# GPRS_GNSS.net
KiCad netlist of a schematic drawn in Altium Designer
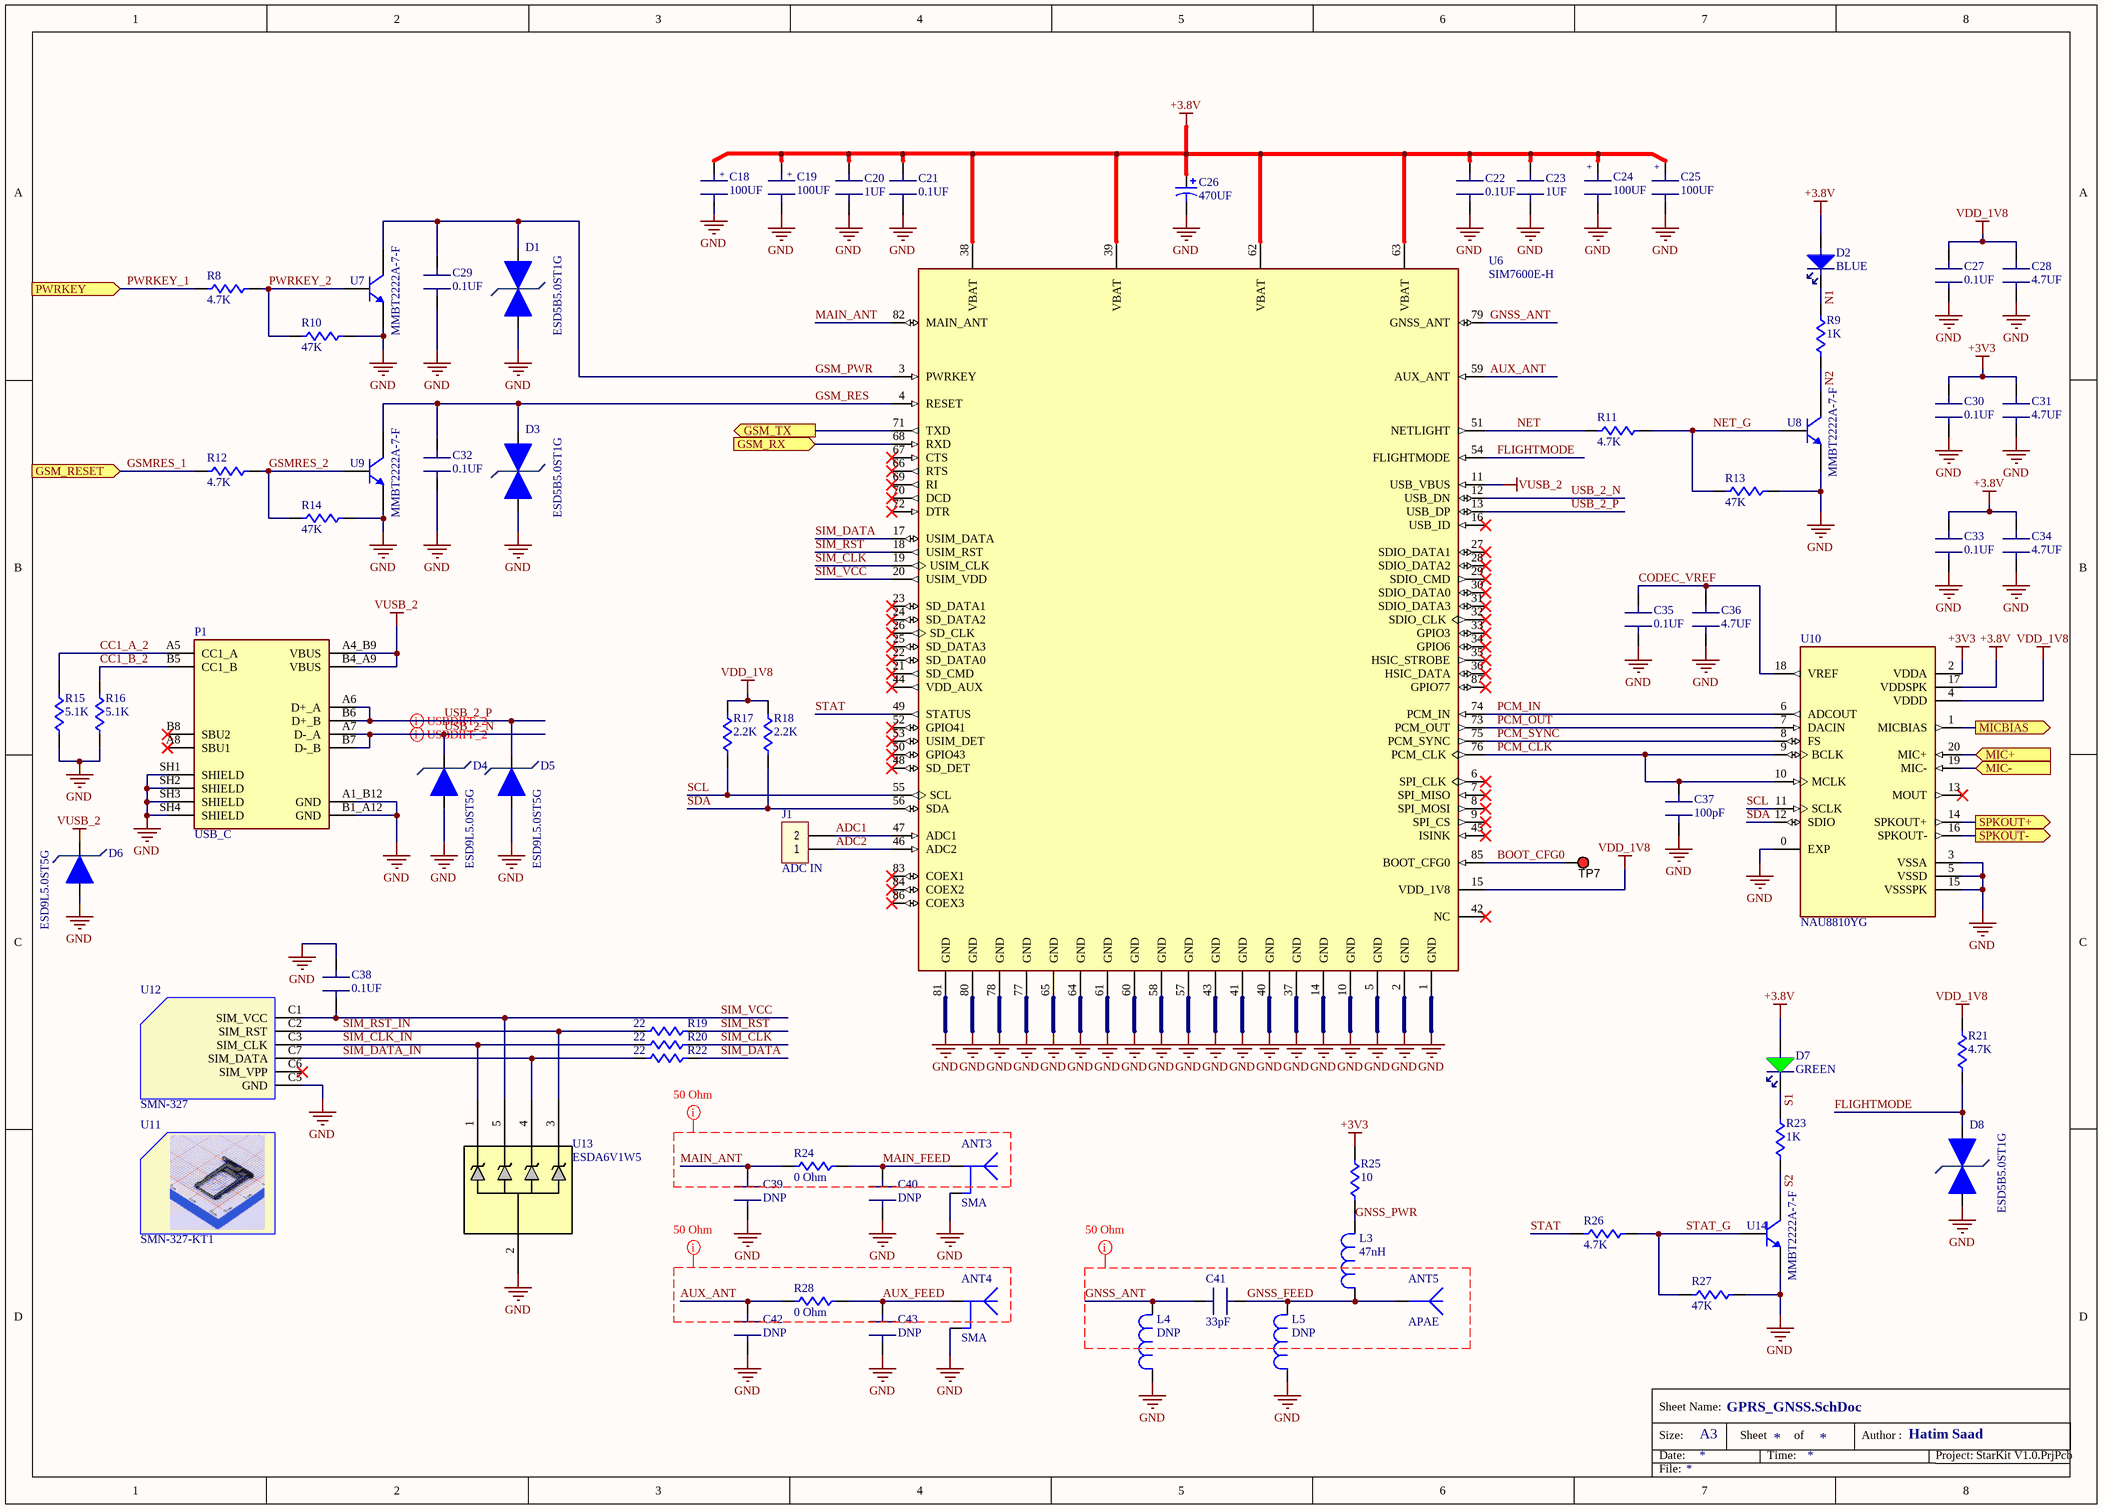
[diagram p0: GPRS_GNSS.SchDoc]

(export (version "E")
  (design (tool "Eeschema 10.0.6"))
  (components
    (comp (ref "ANT3")
      (value "SMA")
      (footprint "SMA RIGHT DIGIKEY")
      (description "Right Angled Female SMA Connector")
      (libsource (lib "HZSchLib") (part "SMA_1"))
    )
    (comp (ref "ANT4")
      (value "SMA")
      (footprint "SMA RIGHT DIGIKEY")
      (description "Right Angled Female SMA Connector")
      (libsource (lib "HZSchLib") (part "SMA_1"))
    )
    (comp (ref "ANT5")
      (value "APAE")
      (footprint "Ceramic Patch Antenna 25x25")
      (description "1575.42MHZ, 25*25*2mm GPS Patch Antenna")
      (fields
        (field (name "MANUFACTURER") "Abracon")
        (field (name "MANUFACTURER PART NUMBER") "APAE1575R2520ABDD7-T")
      )
      (libsource (lib "HZSchLib") (part "APAE1575R2520ABDD7-T"))
    )
    (comp (ref "C18")
      (value "100UF")
      (footprint "CAP: TANTAL-D")
      (description "Tantalum Polymer Capacitor, 100 uF, 16 V, ± 20%, D2, 50 mohm, 2917 [7343-19 Metric]")
      (fields
        (field (name "MANUFACTURER") "Panasonic")
        (field (name "MANUFACTURER PART NUMBER") "16TQC100MYF")
      )
      (libsource (lib "HZSchLib") (part "16TQC100MYF"))
    )
    (comp (ref "C19")
      (value "100UF")
      (footprint "CAP: TANTAL-D")
      (description "Tantalum Polymer Capacitor, 100 uF, 16 V, ± 20%, D2, 50 mohm, 2917 [7343-19 Metric]")
      (fields
        (field (name "MANUFACTURER") "Panasonic")
        (field (name "MANUFACTURER PART NUMBER") "16TQC100MYF")
      )
      (libsource (lib "HZSchLib") (part "16TQC100MYF"))
    )
    (comp (ref "C20")
      (value "1UF")
      (footprint "CAP: 0603")
      (description "CAP SMD 0603")
      (libsource (lib "HZSchLib") (part "CAP 0603"))
    )
    (comp (ref "C21")
      (value "0.1UF")
      (footprint "CAP: 0603")
      (description "CAP SMD 0603")
      (libsource (lib "HZSchLib") (part "CAP 0603"))
    )
    (comp (ref "C22")
      (value "0.1UF")
      (footprint "CAP: 0603")
      (description "CAP SMD 0603")
      (libsource (lib "HZSchLib") (part "CAP 0603"))
    )
    (comp (ref "C23")
      (value "1UF")
      (footprint "CAP: 0603")
      (description "CAP SMD 0603")
      (libsource (lib "HZSchLib") (part "CAP 0603"))
    )
    (comp (ref "C24")
      (value "100UF")
      (footprint "CAP: TANTAL-D")
      (description "Tantalum Polymer Capacitor, 100 uF, 16 V, ± 20%, D2, 50 mohm, 2917 [7343-19 Metric]")
      (fields
        (field (name "MANUFACTURER") "Panasonic")
        (field (name "MANUFACTURER PART NUMBER") "16TQC100MYF")
      )
      (libsource (lib "HZSchLib") (part "16TQC100MYF"))
    )
    (comp (ref "C25")
      (value "100UF")
      (footprint "CAP: TANTAL-D")
      (description "Tantalum Polymer Capacitor, 100 uF, 16 V, ± 20%, D2, 50 mohm, 2917 [7343-19 Metric]")
      (fields
        (field (name "MANUFACTURER") "Panasonic")
        (field (name "MANUFACTURER PART NUMBER") "16TQC100MYF")
      )
      (libsource (lib "HZSchLib") (part "16TQC100MYF"))
    )
    (comp (ref "C26")
      (value "470UF")
      (footprint "CAP POLY: 7.3X4.3X2.8")
      (description "4V 470uF ±20% SMD,4.3x7.3mm Solid Capacitors ROHS")
      (libsource (lib "StarKit V1.0") (part "MPD471M0JD28009R"))
    )
    (comp (ref "C27")
      (value "0.1UF")
      (footprint "CAP: 0603")
      (description "CAP SMD 0603")
      (libsource (lib "HZSchLib") (part "CAP 0603"))
    )
    (comp (ref "C28")
      (value "4.7UF")
      (footprint "CAP: 0805")
      (description "CAP SMD 0805")
      (libsource (lib "HZSchLib") (part "CAP 0805"))
    )
    (comp (ref "C29")
      (value "0.1UF")
      (footprint "CAP: 0603")
      (description "CAP SMD 0603")
      (libsource (lib "HZSchLib") (part "CAP 0603"))
    )
    (comp (ref "C30")
      (value "0.1UF")
      (footprint "CAP: 0603")
      (description "CAP SMD 0603")
      (libsource (lib "HZSchLib") (part "CAP 0603"))
    )
    (comp (ref "C31")
      (value "4.7UF")
      (footprint "CAP: 0805")
      (description "CAP SMD 0805")
      (libsource (lib "HZSchLib") (part "CAP 0805"))
    )
    (comp (ref "C32")
      (value "0.1UF")
      (footprint "CAP: 0603")
      (description "CAP SMD 0603")
      (libsource (lib "HZSchLib") (part "CAP 0603"))
    )
    (comp (ref "C33")
      (value "0.1UF")
      (footprint "CAP: 0603")
      (description "CAP SMD 0603")
      (libsource (lib "HZSchLib") (part "CAP 0603"))
    )
    (comp (ref "C34")
      (value "4.7UF")
      (footprint "CAP: 0805")
      (description "CAP SMD 0805")
      (libsource (lib "HZSchLib") (part "CAP 0805"))
    )
    (comp (ref "C35")
      (value "0.1UF")
      (footprint "CAP: 0603")
      (description "CAP SMD 0603")
      (libsource (lib "HZSchLib") (part "CAP 0603"))
    )
    (comp (ref "C36")
      (value "4.7UF")
      (footprint "CAP: 0805")
      (description "CAP SMD 0805")
      (libsource (lib "HZSchLib") (part "CAP 0805"))
    )
    (comp (ref "C37")
      (value "100pF")
      (footprint "CAP: 0603")
      (description "CAP SMD 0603")
      (libsource (lib "HZSchLib") (part "CAP 0603"))
    )
    (comp (ref "C38")
      (value "0.1UF")
      (footprint "CAP: 0603")
      (description "CAP SMD 0603")
      (libsource (lib "HZSchLib") (part "CAP 0603"))
    )
    (comp (ref "C39")
      (value "DNP")
      (footprint "CAP: 0603")
      (description "CAP SMD 0603")
      (libsource (lib "HZSchLib") (part "CAP 0603"))
    )
    (comp (ref "C40")
      (value "DNP")
      (footprint "CAP: 0603")
      (description "CAP SMD 0603")
      (libsource (lib "HZSchLib") (part "CAP 0603"))
    )
    (comp (ref "C41")
      (value "33pF")
      (footprint "CAP: 0603")
      (description "CAP SMD 0603")
      (libsource (lib "HZSchLib") (part "CAP 0603"))
    )
    (comp (ref "C42")
      (value "DNP")
      (footprint "CAP: 0603")
      (description "CAP SMD 0603")
      (libsource (lib "HZSchLib") (part "CAP 0603"))
    )
    (comp (ref "C43")
      (value "DNP")
      (footprint "CAP: 0603")
      (description "CAP SMD 0603")
      (libsource (lib "HZSchLib") (part "CAP 0603"))
    )
    (comp (ref "D1")
      (value "ESD5B5.0ST1G")
      (footprint "SOD-523-2")
      (description "ESD5B5.0S Series 5.8 V 50 W 32 pF SMT ESD Protection Diode - SOD-523")
      (fields (field (name "MANUFACTURER") "ON Semiconductor"))
      (libsource (lib "HZSchLib") (part "ESD5B5.0ST1G"))
    )
    (comp (ref "D2")
      (value "BLUE")
      (footprint "LED: 0603B")
      (description "LED BLUE CLEAR 0603 SMD")
      (libsource (lib "HZSchLib") (part "LED BLUE 0603"))
    )
    (comp (ref "D3")
      (value "ESD5B5.0ST1G")
      (footprint "SOD-523-2")
      (description "ESD5B5.0S Series 5.8 V 50 W 32 pF SMT ESD Protection Diode - SOD-523")
      (fields (field (name "MANUFACTURER") "ON Semiconductor"))
      (libsource (lib "HZSchLib") (part "ESD5B5.0ST1G"))
    )
    (comp (ref "D4")
      (value "ESD9L5.0ST5G")
      (footprint "SOD-923-2")
      (description "ESD Suppressor Diode TVS Uni-Dir 5V 9.8Vc 2-Pin SOD-923 T/R")
      (fields (field (name "MANUFACTURER") "ON Semiconductor"))
      (libsource (lib "HZSchLib") (part "ESD9L5.0ST5G"))
    )
    (comp (ref "D5")
      (value "ESD9L5.0ST5G")
      (footprint "SOD-923-2")
      (description "ESD Suppressor Diode TVS Uni-Dir 5V 9.8Vc 2-Pin SOD-923 T/R")
      (fields (field (name "MANUFACTURER") "ON Semiconductor"))
      (libsource (lib "HZSchLib") (part "ESD9L5.0ST5G"))
    )
    (comp (ref "D6")
      (value "ESD9L5.0ST5G")
      (footprint "SOD-923-2")
      (description "ESD Suppressor Diode TVS Uni-Dir 5V 9.8Vc 2-Pin SOD-923 T/R")
      (fields (field (name "MANUFACTURER") "ON Semiconductor"))
      (libsource (lib "HZSchLib") (part "ESD9L5.0ST5G"))
    )
    (comp (ref "D7")
      (value "GREEN")
      (footprint "LED: 0603G")
      (description "LED GREEN CLEAR 0603 SMD")
      (libsource (lib "HZSchLib") (part "LED GREEN 0603"))
    )
    (comp (ref "D8")
      (value "ESD5B5.0ST1G")
      (footprint "SOD-523-2")
      (description "ESD5B5.0S Series 5.8 V 50 W 32 pF SMT ESD Protection Diode - SOD-523")
      (fields (field (name "MANUFACTURER") "ON Semiconductor"))
      (libsource (lib "HZSchLib") (part "ESD5B5.0ST1G"))
    )
    (comp (ref "J1")
      (value "ADC IN")
      (footprint "CON: PLS-2")
      (libsource (lib "HZSchLib") (part "CONN 2_HF"))
    )
    (comp (ref "L3")
      (value "47nH")
      (footprint "IND: 0603")
      (description "IND SMD 0603")
      (libsource (lib "HZSchLib") (part "IND 0603"))
    )
    (comp (ref "L4")
      (value "DNP")
      (footprint "IND: 0603")
      (description "IND SMD 0603")
      (libsource (lib "HZSchLib") (part "IND 0603"))
    )
    (comp (ref "L5")
      (value "DNP")
      (footprint "IND: 0603")
      (description "IND SMD 0603")
      (libsource (lib "HZSchLib") (part "IND 0603"))
    )
    (comp (ref "P1")
      (value "USB_C")
      (footprint "AMPHENOL_12402012E212A")
      (description "USB Connectors USB2.0, Type C, Top mount, CH 1.68mm, Dual Row SMT")
      (fields
        (field (name "MANUFACTURER") "Amphenol")
        (field (name "MANUFACTURER PART NUMBER") "12402012E212A")
      )
      (libsource (lib "HZSchLib") (part "12402012E212A"))
    )
    (comp (ref "R8")
      (value "4.7K")
      (footprint "RES: 0603")
      (description "RES SMD 0603")
      (libsource (lib "HZSchLib") (part "RES 0603"))
    )
    (comp (ref "R9")
      (value "1K")
      (footprint "RES: 0603")
      (description "RES SMD 0603")
      (libsource (lib "HZSchLib") (part "RES 0603"))
    )
    (comp (ref "R10")
      (value "47K")
      (footprint "RES: 0603")
      (description "RES SMD 0603")
      (libsource (lib "HZSchLib") (part "RES 0603"))
    )
    (comp (ref "R11")
      (value "4.7K")
      (footprint "RES: 0603")
      (description "RES SMD 0603")
      (libsource (lib "HZSchLib") (part "RES 0603"))
    )
    (comp (ref "R12")
      (value "4.7K")
      (footprint "RES: 0603")
      (description "RES SMD 0603")
      (libsource (lib "HZSchLib") (part "RES 0603"))
    )
    (comp (ref "R13")
      (value "47K")
      (footprint "RES: 0603")
      (description "RES SMD 0603")
      (libsource (lib "HZSchLib") (part "RES 0603"))
    )
    (comp (ref "R14")
      (value "47K")
      (footprint "RES: 0603")
      (description "RES SMD 0603")
      (libsource (lib "HZSchLib") (part "RES 0603"))
    )
    (comp (ref "R15")
      (value "5.1K")
      (footprint "RES: 0603")
      (description "RES SMD 0603")
      (libsource (lib "HZSchLib") (part "RES 0603"))
    )
    (comp (ref "R16")
      (value "5.1K")
      (footprint "RES: 0603")
      (description "RES SMD 0603")
      (libsource (lib "HZSchLib") (part "RES 0603"))
    )
    (comp (ref "R17")
      (value "2.2K")
      (footprint "RES: 0603")
      (description "RES SMD 0603")
      (libsource (lib "HZSchLib") (part "RES 0603"))
    )
    (comp (ref "R18")
      (value "2.2K")
      (footprint "RES: 0603")
      (description "RES SMD 0603")
      (libsource (lib "HZSchLib") (part "RES 0603"))
    )
    (comp (ref "R19")
      (value "22")
      (footprint "RES: 0603")
      (description "RES SMD 0603")
      (libsource (lib "HZSchLib") (part "RES 0603"))
    )
    (comp (ref "R20")
      (value "22")
      (footprint "RES: 0603")
      (description "RES SMD 0603")
      (libsource (lib "HZSchLib") (part "RES 0603"))
    )
    (comp (ref "R21")
      (value "4.7K")
      (footprint "RES: 0603")
      (description "RES SMD 0603")
      (libsource (lib "HZSchLib") (part "RES 0603"))
    )
    (comp (ref "R22")
      (value "22")
      (footprint "RES: 0603")
      (description "RES SMD 0603")
      (libsource (lib "HZSchLib") (part "RES 0603"))
    )
    (comp (ref "R23")
      (value "1K")
      (footprint "RES: 0603")
      (description "RES SMD 0603")
      (libsource (lib "HZSchLib") (part "RES 0603"))
    )
    (comp (ref "R24")
      (value "0 Ohm")
      (footprint "RES: 0603")
      (description "RES SMD 0603")
      (libsource (lib "HZSchLib") (part "RES 0603"))
    )
    (comp (ref "R25")
      (value "10")
      (footprint "RES: 0603")
      (description "RES SMD 0603")
      (libsource (lib "HZSchLib") (part "RES 0603"))
    )
    (comp (ref "R26")
      (value "4.7K")
      (footprint "RES: 0603")
      (description "RES SMD 0603")
      (libsource (lib "HZSchLib") (part "RES 0603"))
    )
    (comp (ref "R27")
      (value "47K")
      (footprint "RES: 0603")
      (description "RES SMD 0603")
      (libsource (lib "HZSchLib") (part "RES 0603"))
    )
    (comp (ref "R28")
      (value "0 Ohm")
      (footprint "RES: 0603")
      (description "RES SMD 0603")
      (libsource (lib "HZSchLib") (part "RES 0603"))
    )
    (comp (ref "TP7")
      (value "5010")
      (footprint "test point")
      (description "Test Point, Multipurpose, Red, TH")
      (fields (field (name "MANUFACTURER") "Keystone") (field (name "PUBLISHER") "Texas Instruments"))
      (libsource (lib "HZSchLib") (part "test point"))
    )
    (comp (ref "U6")
      (value "SIM7600E-H")
      (footprint "SIM7600X")
      (description "RF TXRX MODULE CELLULAR LTE SMD")
      (libsource (lib "HZSchLib") (part "SIM7600E-H"))
    )
    (comp (ref "U7")
      (value "MMBT2222A-7-F")
      (footprint "SOT23_3")
      (description "MMBT2222 Series NPN 350 mW 40 V 600 mA SMT Small Signal Transistor - SOT-23")
      (fields (field (name "MANUFACTURER") "Diodes") (field (name "VOLTAGE") "40V"))
      (libsource (lib "HZSchLib") (part "MMBT2222A-7-F"))
    )
    (comp (ref "U8")
      (value "MMBT2222A-7-F")
      (footprint "SOT23_3")
      (description "MMBT2222 Series NPN 350 mW 40 V 600 mA SMT Small Signal Transistor - SOT-23")
      (fields (field (name "MANUFACTURER") "Diodes") (field (name "VOLTAGE") "40V"))
      (libsource (lib "HZSchLib") (part "MMBT2222A-7-F"))
    )
    (comp (ref "U9")
      (value "MMBT2222A-7-F")
      (footprint "SOT23_3")
      (description "MMBT2222 Series NPN 350 mW 40 V 600 mA SMT Small Signal Transistor - SOT-23")
      (fields (field (name "MANUFACTURER") "Diodes") (field (name "VOLTAGE") "40V"))
      (libsource (lib "HZSchLib") (part "MMBT2222A-7-F"))
    )
    (comp (ref "U10")
      (value "NAU8810YG")
      (footprint "20-QFN (4x4)")
      (description "IC Audio Codec Mono 20QFN")
      (fields (field (name "MANUFACTURER") "Nuvoton"))
      (libsource (lib "HZSchLib") (part "NAU8810YG"))
    )
    (comp (ref "U11")
      (value "SMN-327-KT1")
      (description "NanoSIM tray SIM Card Connectors")
      (fields (field (name "PUBLISHER") "Bastam Beyrami"))
      (libsource (lib "HZSchLib") (part "C390998"))
    )
    (comp (ref "U12")
      (value "SMN-327")
      (footprint "SIM_NANO_SMN-327")
      (description "NanoSIM SMD SIM Card Connectors")
      (fields (field (name "PUBLISHER") "Bastam Beyrami"))
      (libsource (lib "HZSchLib") (part "C390997"))
    )
    (comp (ref "U13")
      (value "ESDA6V1W5")
      (footprint "SOT323-5L")
      (description "ESDA Series 4 Channel 6.1V 90 pF SMT Uni-Directional Transil Array - SOT-323-5L")
      (fields (field (name "MANUFACTURER") "STMicroelectronics"))
      (libsource (lib "HZSchLib") (part "ESDA6V1W5"))
    )
    (comp (ref "U14")
      (value "MMBT2222A-7-F")
      (footprint "SOT23_3")
      (description "MMBT2222 Series NPN 350 mW 40 V 600 mA SMT Small Signal Transistor - SOT-23")
      (fields (field (name "MANUFACTURER") "Diodes") (field (name "VOLTAGE") "40V"))
      (libsource (lib "HZSchLib") (part "MMBT2222A-7-F"))
    )
  )
  (nets
    (net (code "1") (name "+3.8V") (class "Default")
      (node (ref "C18") (pin "1") (pinfunction "+_1") (pintype "passive"))
      (node (ref "C19") (pin "1") (pinfunction "+_1") (pintype "passive"))
      (node (ref "C20") (pin "1") (pinfunction "A_1") (pintype "passive"))
      (node (ref "C21") (pin "1") (pinfunction "A_1") (pintype "passive"))
      (node (ref "C22") (pin "1") (pinfunction "A_1") (pintype "passive"))
      (node (ref "C23") (pin "1") (pinfunction "A_1") (pintype "passive"))
      (node (ref "C24") (pin "1") (pinfunction "+_1") (pintype "passive"))
      (node (ref "C25") (pin "1") (pinfunction "+_1") (pintype "passive"))
      (node (ref "C26") (pin "1") (pinfunction "1_1") (pintype "passive"))
      (node (ref "C33") (pin "1") (pinfunction "A_1") (pintype "passive"))
      (node (ref "C34") (pin "2") (pinfunction "B_2") (pintype "passive"))
      (node (ref "D2") (pin "2") (pinfunction "A_2") (pintype "passive"))
      (node (ref "D7") (pin "2") (pinfunction "A_2") (pintype "passive"))
      (node (ref "U10") (pin "17") (pinfunction "VDDSPK_17") (pintype "power_in"))
      (node (ref "U6") (pin "38") (pinfunction "VBAT_38") (pintype "power_in"))
      (node (ref "U6") (pin "39") (pinfunction "VBAT_39") (pintype "power_in"))
      (node (ref "U6") (pin "62") (pinfunction "VBAT_62") (pintype "power_in"))
      (node (ref "U6") (pin "63") (pinfunction "VBAT_63") (pintype "power_in"))
    )
    (net (code "2") (name "+3V3") (class "Default")
      (node (ref "C30") (pin "1") (pinfunction "A_1") (pintype "passive"))
      (node (ref "C31") (pin "2") (pinfunction "B_2") (pintype "passive"))
      (node (ref "R25") (pin "2") (pinfunction "2_2") (pintype "passive"))
      (node (ref "U10") (pin "2") (pinfunction "VDDA_2") (pintype "power_in"))
    )
    (net (code "3") (name "/ADC1") (class "Default")
      (node (ref "J1") (pin "2") (pinfunction "2_2") (pintype "power_in"))
      (node (ref "U6") (pin "47") (pinfunction "ADC1_47") (pintype "input"))
    )
    (net (code "4") (name "/ADC2") (class "Default")
      (node (ref "J1") (pin "1") (pinfunction "1_1") (pintype "passive"))
      (node (ref "U6") (pin "46") (pinfunction "ADC2_46") (pintype "input"))
    )
    (net (code "5") (name "/AUX_ANT") (class "Default")
      (node (ref "C42") (pin "1") (pinfunction "A_1") (pintype "passive"))
      (node (ref "R28") (pin "1") (pinfunction "1_1") (pintype "passive"))
      (node (ref "U6") (pin "59") (pinfunction "AUX_ANT_59") (pintype "input"))
    )
    (net (code "6") (name "/AUX_FEED") (class "Default")
      (node (ref "ANT4") (pin "1") (pinfunction "1_1") (pintype "passive"))
      (node (ref "C43") (pin "1") (pinfunction "A_1") (pintype "passive"))
      (node (ref "R28") (pin "2") (pinfunction "2_2") (pintype "passive"))
    )
    (net (code "7") (name "/BOOT_CFG0") (class "Default")
      (node (ref "TP7") (pin "1") (pintype "passive"))
      (node (ref "U6") (pin "85") (pinfunction "BOOT_CFG0_85") (pintype "input"))
    )
    (net (code "8") (name "/CC1_A_2") (class "Default")
      (node (ref "P1") (pin "A5") (pinfunction "CC1_A_A5") (pintype "passive"))
      (node (ref "R15") (pin "2") (pinfunction "2_2") (pintype "passive"))
    )
    (net (code "9") (name "/CC1_B_2") (class "Default")
      (node (ref "P1") (pin "B5") (pinfunction "CC1_B_B5") (pintype "passive"))
      (node (ref "R16") (pin "2") (pinfunction "2_2") (pintype "passive"))
    )
    (net (code "10") (name "/CODEC_VREF") (class "Default")
      (node (ref "C35") (pin "1") (pinfunction "A_1") (pintype "passive"))
      (node (ref "C36") (pin "2") (pinfunction "B_2") (pintype "passive"))
      (node (ref "U10") (pin "18") (pinfunction "VREF_18") (pintype "output"))
    )
    (net (code "11") (name "/FLIGHTMODE") (class "Default")
      (node (ref "D8") (pin "1") (pinfunction "1_1") (pintype "passive"))
      (node (ref "R21") (pin "1") (pinfunction "1_1") (pintype "passive"))
      (node (ref "U6") (pin "54") (pinfunction "FLIGHTMODE_54") (pintype "input"))
    )
    (net (code "12") (name "/GNSS_ANT") (class "Default")
      (node (ref "C41") (pin "1") (pinfunction "A_1") (pintype "passive"))
      (node (ref "L4") (pin "2") (pinfunction "2_2") (pintype "passive"))
      (node (ref "U6") (pin "79") (pinfunction "GNSS_ANT_79") (pintype "bidirectional"))
    )
    (net (code "13") (name "/GNSS_FEED") (class "Default")
      (node (ref "ANT5") (pin "1") (pinfunction "1_1") (pintype "passive"))
      (node (ref "C41") (pin "2") (pinfunction "B_2") (pintype "passive"))
      (node (ref "L3") (pin "1") (pinfunction "1_1") (pintype "passive"))
      (node (ref "L5") (pin "2") (pinfunction "2_2") (pintype "passive"))
    )
    (net (code "14") (name "/GNSS_PWR") (class "Default")
      (node (ref "L3") (pin "2") (pinfunction "2_2") (pintype "passive"))
      (node (ref "R25") (pin "1") (pinfunction "1_1") (pintype "passive"))
    )
    (net (code "15") (name "/GSMRES_1") (class "Default")
      (node (ref "R12") (pin "1") (pinfunction "1_1") (pintype "passive"))
    )
    (net (code "16") (name "/GSMRES_2") (class "Default")
      (node (ref "R12") (pin "2") (pinfunction "2_2") (pintype "passive"))
      (node (ref "R14") (pin "1") (pinfunction "1_1") (pintype "passive"))
      (node (ref "U9") (pin "1") (pinfunction "B_1") (pintype "passive"))
    )
    (net (code "17") (name "/GSM_PWR") (class "Default")
      (node (ref "C29") (pin "1") (pinfunction "A_1") (pintype "passive"))
      (node (ref "D1") (pin "1") (pinfunction "1_1") (pintype "passive"))
      (node (ref "U6") (pin "3") (pinfunction "PWRKEY_3") (pintype "input"))
      (node (ref "U7") (pin "3") (pinfunction "C_3") (pintype "passive"))
    )
    (net (code "18") (name "/GSM_RES") (class "Default")
      (node (ref "C32") (pin "1") (pinfunction "A_1") (pintype "passive"))
      (node (ref "D3") (pin "1") (pinfunction "1_1") (pintype "passive"))
      (node (ref "U6") (pin "4") (pinfunction "RESET_4") (pintype "input"))
      (node (ref "U9") (pin "3") (pinfunction "C_3") (pintype "passive"))
    )
    (net (code "19") (name "/GSM_RX") (class "Default")
      (node (ref "U6") (pin "68") (pinfunction "RXD_68") (pintype "input"))
    )
    (net (code "20") (name "/GSM_TX") (class "Default")
      (node (ref "U6") (pin "71") (pinfunction "TXD_71") (pintype "output"))
    )
    (net (code "21") (name "/MAIN_ANT") (class "Default")
      (node (ref "C39") (pin "1") (pinfunction "A_1") (pintype "passive"))
      (node (ref "R24") (pin "1") (pinfunction "1_1") (pintype "passive"))
      (node (ref "U6") (pin "82") (pinfunction "MAIN_ANT_82") (pintype "bidirectional"))
    )
    (net (code "22") (name "/MAIN_FEED") (class "Default")
      (node (ref "ANT3") (pin "1") (pinfunction "1_1") (pintype "passive"))
      (node (ref "C40") (pin "1") (pinfunction "A_1") (pintype "passive"))
      (node (ref "R24") (pin "2") (pinfunction "2_2") (pintype "passive"))
    )
    (net (code "23") (name "/MIC+") (class "Default")
      (node (ref "U10") (pin "20") (pinfunction "MIC+_20") (pintype "input"))
    )
    (net (code "24") (name "/MIC-") (class "Default")
      (node (ref "U10") (pin "19") (pinfunction "MIC-_19") (pintype "input"))
    )
    (net (code "25") (name "/MICBIAS") (class "Default")
      (node (ref "U10") (pin "1") (pinfunction "MICBIAS_1") (pintype "output"))
    )
    (net (code "26") (name "/N1") (class "Default")
      (node (ref "D2") (pin "1") (pinfunction "C_1") (pintype "passive"))
      (node (ref "R9") (pin "2") (pinfunction "2_2") (pintype "passive"))
    )
    (net (code "27") (name "/N2") (class "Default")
      (node (ref "R9") (pin "1") (pinfunction "1_1") (pintype "passive"))
      (node (ref "U8") (pin "3") (pinfunction "C_3") (pintype "passive"))
    )
    (net (code "28") (name "/NET") (class "Default")
      (node (ref "R11") (pin "1") (pinfunction "1_1") (pintype "passive"))
      (node (ref "U6") (pin "51") (pinfunction "NETLIGHT_51") (pintype "output"))
    )
    (net (code "29") (name "/NET_G") (class "Default")
      (node (ref "R11") (pin "2") (pinfunction "2_2") (pintype "passive"))
      (node (ref "R13") (pin "1") (pinfunction "1_1") (pintype "passive"))
      (node (ref "U8") (pin "1") (pinfunction "B_1") (pintype "passive"))
    )
    (net (code "30") (name "/PCM_CLK") (class "Default")
      (node (ref "C37") (pin "1") (pinfunction "A_1") (pintype "passive"))
      (node (ref "U10") (pin "10") (pinfunction "MCLK_10") (pintype "input"))
      (node (ref "U10") (pin "9") (pinfunction "BCLK_9") (pintype "bidirectional"))
      (node (ref "U6") (pin "76") (pinfunction "PCM_CLK_76") (pintype "output"))
    )
    (net (code "31") (name "/PCM_IN") (class "Default")
      (node (ref "U10") (pin "6") (pinfunction "ADCOUT_6") (pintype "output"))
      (node (ref "U6") (pin "74") (pinfunction "PCM_IN_74") (pintype "input"))
    )
    (net (code "32") (name "/PCM_OUT") (class "Default")
      (node (ref "U10") (pin "7") (pinfunction "DACIN_7") (pintype "input"))
      (node (ref "U6") (pin "73") (pinfunction "PCM_OUT_73") (pintype "output"))
    )
    (net (code "33") (name "/PCM_SYNC") (class "Default")
      (node (ref "U10") (pin "8") (pinfunction "FS_8") (pintype "bidirectional"))
      (node (ref "U6") (pin "75") (pinfunction "PCM_SYNC_75") (pintype "output"))
    )
    (net (code "34") (name "/PWRKEY_1") (class "Default")
      (node (ref "R8") (pin "1") (pinfunction "1_1") (pintype "passive"))
    )
    (net (code "35") (name "/PWRKEY_2") (class "Default")
      (node (ref "R10") (pin "1") (pinfunction "1_1") (pintype "passive"))
      (node (ref "R8") (pin "2") (pinfunction "2_2") (pintype "passive"))
      (node (ref "U7") (pin "1") (pinfunction "B_1") (pintype "passive"))
    )
    (net (code "36") (name "/S1") (class "Default")
      (node (ref "D7") (pin "1") (pinfunction "C_1") (pintype "passive"))
      (node (ref "R23") (pin "2") (pinfunction "2_2") (pintype "passive"))
    )
    (net (code "37") (name "/S2") (class "Default")
      (node (ref "R23") (pin "1") (pinfunction "1_1") (pintype "passive"))
      (node (ref "U14") (pin "3") (pinfunction "C_3") (pintype "passive"))
    )
    (net (code "38") (name "/SCL") (class "Default")
      (node (ref "R17") (pin "1") (pinfunction "1_1") (pintype "passive"))
      (node (ref "U10") (pin "11") (pinfunction "SCLK_11") (pintype "input"))
      (node (ref "U6") (pin "55") (pinfunction "SCL_55") (pintype "output"))
    )
    (net (code "39") (name "/SDA") (class "Default")
      (node (ref "R18") (pin "1") (pinfunction "1_1") (pintype "passive"))
      (node (ref "U10") (pin "12") (pinfunction "SDIO_12") (pintype "bidirectional"))
      (node (ref "U6") (pin "56") (pinfunction "SDA_56") (pintype "bidirectional"))
    )
    (net (code "40") (name "/SIM_CLK") (class "Default")
      (node (ref "R20") (pin "2") (pinfunction "2_2") (pintype "passive"))
      (node (ref "U6") (pin "19") (pinfunction "USIM_CLK_19") (pintype "output"))
    )
    (net (code "41") (name "/SIM_CLK_IN") (class "Default")
      (node (ref "R20") (pin "1") (pinfunction "1_1") (pintype "passive"))
      (node (ref "U12") (pin "C3") (pinfunction "SIM_CLK_C3") (pintype "passive"))
      (node (ref "U13") (pin "1") (pinfunction "1_1") (pintype "passive"))
    )
    (net (code "42") (name "/SIM_DATA") (class "Default")
      (node (ref "R22") (pin "2") (pinfunction "2_2") (pintype "passive"))
      (node (ref "U6") (pin "17") (pinfunction "USIM_DATA_17") (pintype "bidirectional"))
    )
    (net (code "43") (name "/SIM_DATA_IN") (class "Default")
      (node (ref "R22") (pin "1") (pinfunction "1_1") (pintype "passive"))
      (node (ref "U12") (pin "C7") (pinfunction "SIM_DATA_C7") (pintype "passive"))
      (node (ref "U13") (pin "4") (pinfunction "4_4") (pintype "passive"))
    )
    (net (code "44") (name "/SIM_RST") (class "Default")
      (node (ref "R19") (pin "2") (pinfunction "2_2") (pintype "passive"))
      (node (ref "U6") (pin "18") (pinfunction "USIM_RST_18") (pintype "output"))
    )
    (net (code "45") (name "/SIM_RST_IN") (class "Default")
      (node (ref "R19") (pin "1") (pinfunction "1_1") (pintype "passive"))
      (node (ref "U12") (pin "C2") (pinfunction "SIM_RST_C2") (pintype "passive"))
      (node (ref "U13") (pin "3") (pinfunction "3_3") (pintype "passive"))
    )
    (net (code "46") (name "/SIM_VCC") (class "Default")
      (node (ref "C38") (pin "2") (pinfunction "B_2") (pintype "passive"))
      (node (ref "U12") (pin "C1") (pinfunction "SIM_VCC_C1") (pintype "passive"))
      (node (ref "U13") (pin "5") (pinfunction "5_5") (pintype "passive"))
      (node (ref "U6") (pin "20") (pinfunction "USIM_VDD_20") (pintype "output"))
    )
    (net (code "47") (name "/SPKOUT+") (class "Default")
      (node (ref "U10") (pin "14") (pinfunction "SPKOUT+_14") (pintype "output"))
    )
    (net (code "48") (name "/SPKOUT-") (class "Default")
      (node (ref "U10") (pin "16") (pinfunction "SPKOUT-_16") (pintype "output"))
    )
    (net (code "49") (name "/STAT") (class "Default")
      (node (ref "R26") (pin "1") (pinfunction "1_1") (pintype "passive"))
      (node (ref "U6") (pin "49") (pinfunction "STATUS_49") (pintype "output"))
    )
    (net (code "50") (name "/STAT_G") (class "Default")
      (node (ref "R26") (pin "2") (pinfunction "2_2") (pintype "passive"))
      (node (ref "R27") (pin "1") (pinfunction "1_1") (pintype "passive"))
      (node (ref "U14") (pin "1") (pinfunction "B_1") (pintype "passive"))
    )
    (net (code "51") (name "/USB_2_N") (class "Default")
      (node (ref "D4") (pin "1") (pinfunction "1_1") (pintype "passive"))
      (node (ref "P1") (pin "A7") (pinfunction "D-_A_A7") (pintype "passive"))
      (node (ref "P1") (pin "B7") (pinfunction "D-_B_B7") (pintype "passive"))
      (node (ref "U6") (pin "12") (pinfunction "USB_DN_12") (pintype "bidirectional"))
    )
    (net (code "52") (name "/USB_2_P") (class "Default")
      (node (ref "D5") (pin "1") (pinfunction "1_1") (pintype "passive"))
      (node (ref "P1") (pin "A6") (pinfunction "D+_A_A6") (pintype "passive"))
      (node (ref "P1") (pin "B6") (pinfunction "D+_B_B6") (pintype "passive"))
      (node (ref "U6") (pin "13") (pinfunction "USB_DP_13") (pintype "bidirectional"))
    )
    (net (code "53") (name "GND") (class "Default")
      (node (ref "ANT3") (pin "2") (pinfunction "2_2") (pintype "passive"))
      (node (ref "ANT4") (pin "2") (pinfunction "2_2") (pintype "passive"))
      (node (ref "C18") (pin "2") (pinfunction "-_2") (pintype "passive"))
      (node (ref "C19") (pin "2") (pinfunction "-_2") (pintype "passive"))
      (node (ref "C20") (pin "2") (pinfunction "B_2") (pintype "passive"))
      (node (ref "C21") (pin "2") (pinfunction "B_2") (pintype "passive"))
      (node (ref "C22") (pin "2") (pinfunction "B_2") (pintype "passive"))
      (node (ref "C23") (pin "2") (pinfunction "B_2") (pintype "passive"))
      (node (ref "C24") (pin "2") (pinfunction "-_2") (pintype "passive"))
      (node (ref "C25") (pin "2") (pinfunction "-_2") (pintype "passive"))
      (node (ref "C26") (pin "2") (pinfunction "2_2") (pintype "passive"))
      (node (ref "C27") (pin "2") (pinfunction "B_2") (pintype "passive"))
      (node (ref "C28") (pin "1") (pinfunction "A_1") (pintype "passive"))
      (node (ref "C29") (pin "2") (pinfunction "B_2") (pintype "passive"))
      (node (ref "C30") (pin "2") (pinfunction "B_2") (pintype "passive"))
      (node (ref "C31") (pin "1") (pinfunction "A_1") (pintype "passive"))
      (node (ref "C32") (pin "2") (pinfunction "B_2") (pintype "passive"))
      (node (ref "C33") (pin "2") (pinfunction "B_2") (pintype "passive"))
      (node (ref "C34") (pin "1") (pinfunction "A_1") (pintype "passive"))
      (node (ref "C35") (pin "2") (pinfunction "B_2") (pintype "passive"))
      (node (ref "C36") (pin "1") (pinfunction "A_1") (pintype "passive"))
      (node (ref "C37") (pin "2") (pinfunction "B_2") (pintype "passive"))
      (node (ref "C38") (pin "1") (pinfunction "A_1") (pintype "passive"))
      (node (ref "C39") (pin "2") (pinfunction "B_2") (pintype "passive"))
      (node (ref "C40") (pin "2") (pinfunction "B_2") (pintype "passive"))
      (node (ref "C42") (pin "2") (pinfunction "B_2") (pintype "passive"))
      (node (ref "C43") (pin "2") (pinfunction "B_2") (pintype "passive"))
      (node (ref "D1") (pin "2") (pinfunction "2_2") (pintype "passive"))
      (node (ref "D3") (pin "2") (pinfunction "2_2") (pintype "passive"))
      (node (ref "D4") (pin "2") (pinfunction "2_2") (pintype "passive"))
      (node (ref "D5") (pin "2") (pinfunction "2_2") (pintype "passive"))
      (node (ref "D6") (pin "2") (pinfunction "2_2") (pintype "passive"))
      (node (ref "D8") (pin "2") (pinfunction "2_2") (pintype "passive"))
      (node (ref "L4") (pin "1") (pinfunction "1_1") (pintype "passive"))
      (node (ref "L5") (pin "1") (pinfunction "1_1") (pintype "passive"))
      (node (ref "P1") (pin "A1_B12") (pinfunction "GND_A1_B12") (pintype "passive"))
      (node (ref "P1") (pin "B1_A12") (pinfunction "GND_B1_A12") (pintype "passive"))
      (node (ref "P1") (pin "SH1") (pinfunction "SHIELD_SH1") (pintype "passive"))
      (node (ref "P1") (pin "SH2") (pinfunction "SHIELD_SH2") (pintype "passive"))
      (node (ref "P1") (pin "SH3") (pinfunction "SHIELD_SH3") (pintype "passive"))
      (node (ref "P1") (pin "SH4") (pinfunction "SHIELD_SH4") (pintype "passive"))
      (node (ref "R10") (pin "2") (pinfunction "2_2") (pintype "passive"))
      (node (ref "R13") (pin "2") (pinfunction "2_2") (pintype "passive"))
      (node (ref "R14") (pin "2") (pinfunction "2_2") (pintype "passive"))
      (node (ref "R15") (pin "1") (pinfunction "1_1") (pintype "passive"))
      (node (ref "R16") (pin "1") (pinfunction "1_1") (pintype "passive"))
      (node (ref "R27") (pin "2") (pinfunction "2_2") (pintype "passive"))
      (node (ref "U10") (pin "0") (pinfunction "EXP_0") (pintype "passive"))
      (node (ref "U10") (pin "15") (pinfunction "VSSSPK_15") (pintype "power_in"))
      (node (ref "U10") (pin "3") (pinfunction "VSSA_3") (pintype "power_in"))
      (node (ref "U10") (pin "5") (pinfunction "VSSD_5") (pintype "power_in"))
      (node (ref "U12") (pin "C5") (pinfunction "GND_C5") (pintype "passive"))
      (node (ref "U13") (pin "2") (pinfunction "2_2") (pintype "passive"))
      (node (ref "U14") (pin "2") (pinfunction "E_2") (pintype "passive"))
      (node (ref "U6") (pin "1") (pinfunction "GND_1") (pintype "power_in"))
      (node (ref "U6") (pin "10") (pinfunction "GND_10") (pintype "power_in"))
      (node (ref "U6") (pin "14") (pinfunction "GND_14") (pintype "power_in"))
      (node (ref "U6") (pin "2") (pinfunction "GND_2") (pintype "power_in"))
      (node (ref "U6") (pin "37") (pinfunction "GND_37") (pintype "power_in"))
      (node (ref "U6") (pin "40") (pinfunction "GND_40") (pintype "power_in"))
      (node (ref "U6") (pin "41") (pinfunction "GND_41") (pintype "power_in"))
      (node (ref "U6") (pin "43") (pinfunction "GND_43") (pintype "power_in"))
      (node (ref "U6") (pin "5") (pinfunction "GND_5") (pintype "power_in"))
      (node (ref "U6") (pin "57") (pinfunction "GND_57") (pintype "power_in"))
      (node (ref "U6") (pin "58") (pinfunction "GND_58") (pintype "power_in"))
      (node (ref "U6") (pin "60") (pinfunction "GND_60") (pintype "power_in"))
      (node (ref "U6") (pin "61") (pinfunction "GND_61") (pintype "power_in"))
      (node (ref "U6") (pin "64") (pinfunction "GND_64") (pintype "power_in"))
      (node (ref "U6") (pin "65") (pinfunction "GND_65") (pintype "power_in"))
      (node (ref "U6") (pin "77") (pinfunction "GND_77") (pintype "power_in"))
      (node (ref "U6") (pin "78") (pinfunction "GND_78") (pintype "power_in"))
      (node (ref "U6") (pin "80") (pinfunction "GND_80") (pintype "power_in"))
      (node (ref "U6") (pin "81") (pinfunction "GND_81") (pintype "power_in"))
      (node (ref "U7") (pin "2") (pinfunction "E_2") (pintype "passive"))
      (node (ref "U8") (pin "2") (pinfunction "E_2") (pintype "passive"))
      (node (ref "U9") (pin "2") (pinfunction "E_2") (pintype "passive"))
    )
    (net (code "54") (name "VDD_1V8") (class "Default")
      (node (ref "C27") (pin "1") (pinfunction "A_1") (pintype "passive"))
      (node (ref "C28") (pin "2") (pinfunction "B_2") (pintype "passive"))
      (node (ref "R17") (pin "2") (pinfunction "2_2") (pintype "passive"))
      (node (ref "R18") (pin "2") (pinfunction "2_2") (pintype "passive"))
      (node (ref "R21") (pin "2") (pinfunction "2_2") (pintype "passive"))
      (node (ref "U10") (pin "4") (pinfunction "VDDD_4") (pintype "power_in"))
      (node (ref "U6") (pin "15") (pinfunction "VDD_1V8_15") (pintype "power_in"))
    )
    (net (code "55") (name "VUSB_2") (class "Default")
      (node (ref "D6") (pin "1") (pinfunction "1_1") (pintype "passive"))
      (node (ref "P1") (pin "A4_B9") (pinfunction "VBUS_A4_B9") (pintype "passive"))
      (node (ref "P1") (pin "B4_A9") (pinfunction "VBUS_B4_A9") (pintype "passive"))
      (node (ref "U6") (pin "11") (pinfunction "USB_VBUS_11") (pintype "input"))
    )
    (net (code "56") (name "unconnected-(P1-SBU1-PadA8)") (class "Default")
      (node (ref "P1") (pin "A8") (pinfunction "SBU1_A8") (pintype "passive+no_connect"))
    )
    (net (code "57") (name "unconnected-(P1-SBU2-PadB8)") (class "Default")
      (node (ref "P1") (pin "B8") (pinfunction "SBU2_B8") (pintype "passive+no_connect"))
    )
    (net (code "58") (name "unconnected-(U6-COEX1-Pad83)") (class "Default")
      (node (ref "U6") (pin "83") (pinfunction "COEX1_83") (pintype "bidirectional+no_connect"))
    )
    (net (code "59") (name "unconnected-(U6-COEX2-Pad84)") (class "Default")
      (node (ref "U6") (pin "84") (pinfunction "COEX2_84") (pintype "bidirectional+no_connect"))
    )
    (net (code "60") (name "unconnected-(U6-COEX3-Pad86)") (class "Default")
      (node (ref "U6") (pin "86") (pinfunction "COEX3_86") (pintype "bidirectional+no_connect"))
    )
    (net (code "61") (name "unconnected-(U6-CTS-Pad67)") (class "Default")
      (node (ref "U6") (pin "67") (pinfunction "CTS_67") (pintype "input+no_connect"))
    )
    (net (code "62") (name "unconnected-(U6-DCD-Pad70)") (class "Default")
      (node (ref "U6") (pin "70") (pinfunction "DCD_70") (pintype "output+no_connect"))
    )
    (net (code "63") (name "unconnected-(U6-DTR-Pad72)") (class "Default")
      (node (ref "U6") (pin "72") (pinfunction "DTR_72") (pintype "input+no_connect"))
    )
    (net (code "64") (name "unconnected-(U6-GPIO3-Pad33)") (class "Default")
      (node (ref "U6") (pin "33") (pinfunction "GPIO3_33") (pintype "bidirectional+no_connect"))
    )
    (net (code "65") (name "unconnected-(U6-GPIO6-Pad34)") (class "Default")
      (node (ref "U6") (pin "34") (pinfunction "GPIO6_34") (pintype "bidirectional+no_connect"))
    )
    (net (code "66") (name "unconnected-(U6-GPIO41-Pad52)") (class "Default")
      (node (ref "U6") (pin "52") (pinfunction "GPIO41_52") (pintype "bidirectional+no_connect"))
    )
    (net (code "67") (name "unconnected-(U6-GPIO43-Pad50)") (class "Default")
      (node (ref "U6") (pin "50") (pinfunction "GPIO43_50") (pintype "bidirectional+no_connect"))
    )
    (net (code "68") (name "unconnected-(U6-GPIO77-Pad87)") (class "Default")
      (node (ref "U6") (pin "87") (pinfunction "GPIO77_87") (pintype "bidirectional+no_connect"))
    )
    (net (code "69") (name "unconnected-(U6-HSIC_DATA-Pad36)") (class "Default")
      (node (ref "U6") (pin "36") (pinfunction "HSIC_DATA_36") (pintype "bidirectional+no_connect"))
    )
    (net (code "70") (name "unconnected-(U6-HSIC_STROBE-Pad35)") (class "Default")
      (node (ref "U6") (pin "35") (pinfunction "HSIC_STROBE_35") (pintype "output+no_connect"))
    )
    (net (code "71") (name "unconnected-(U6-ISINK-Pad45)") (class "Default")
      (node (ref "U6") (pin "45") (pinfunction "ISINK_45") (pintype "input+no_connect"))
    )
    (net (code "72") (name "unconnected-(U6-NC-Pad42)") (class "Default")
      (node (ref "U6") (pin "42") (pinfunction "NC_42") (pintype "passive+no_connect"))
    )
    (net (code "73") (name "unconnected-(U6-RI-Pad69)") (class "Default")
      (node (ref "U6") (pin "69") (pinfunction "RI_69") (pintype "output+no_connect"))
    )
    (net (code "74") (name "unconnected-(U6-RTS-Pad66)") (class "Default")
      (node (ref "U6") (pin "66") (pinfunction "RTS_66") (pintype "output+no_connect"))
    )
    (net (code "75") (name "unconnected-(U6-SDIO_CLK-Pad32)") (class "Default")
      (node (ref "U6") (pin "32") (pinfunction "SDIO_CLK_32") (pintype "output+no_connect"))
    )
    (net (code "76") (name "unconnected-(U6-SDIO_CMD-Pad29)") (class "Default")
      (node (ref "U6") (pin "29") (pinfunction "SDIO_CMD_29") (pintype "output+no_connect"))
    )
    (net (code "77") (name "unconnected-(U6-SDIO_DATA0-Pad30)") (class "Default")
      (node (ref "U6") (pin "30") (pinfunction "SDIO_DATA0_30") (pintype "bidirectional+no_connect"))
    )
    (net (code "78") (name "unconnected-(U6-SDIO_DATA1-Pad27)") (class "Default")
      (node (ref "U6") (pin "27") (pinfunction "SDIO_DATA1_27") (pintype "bidirectional+no_connect"))
    )
    (net (code "79") (name "unconnected-(U6-SDIO_DATA2-Pad28)") (class "Default")
      (node (ref "U6") (pin "28") (pinfunction "SDIO_DATA2_28") (pintype "bidirectional+no_connect"))
    )
    (net (code "80") (name "unconnected-(U6-SDIO_DATA3-Pad31)") (class "Default")
      (node (ref "U6") (pin "31") (pinfunction "SDIO_DATA3_31") (pintype "bidirectional+no_connect"))
    )
    (net (code "81") (name "unconnected-(U6-SD_CLK-Pad26)") (class "Default")
      (node (ref "U6") (pin "26") (pinfunction "SD_CLK_26") (pintype "output+no_connect"))
    )
    (net (code "82") (name "unconnected-(U6-SD_CMD-Pad21)") (class "Default")
      (node (ref "U6") (pin "21") (pinfunction "SD_CMD_21") (pintype "output+no_connect"))
    )
    (net (code "83") (name "unconnected-(U6-SD_DATA0-Pad22)") (class "Default")
      (node (ref "U6") (pin "22") (pinfunction "SD_DATA0_22") (pintype "bidirectional+no_connect"))
    )
    (net (code "84") (name "unconnected-(U6-SD_DATA1-Pad23)") (class "Default")
      (node (ref "U6") (pin "23") (pinfunction "SD_DATA1_23") (pintype "bidirectional+no_connect"))
    )
    (net (code "85") (name "unconnected-(U6-SD_DATA2-Pad24)") (class "Default")
      (node (ref "U6") (pin "24") (pinfunction "SD_DATA2_24") (pintype "bidirectional+no_connect"))
    )
    (net (code "86") (name "unconnected-(U6-SD_DATA3-Pad25)") (class "Default")
      (node (ref "U6") (pin "25") (pinfunction "SD_DATA3_25") (pintype "bidirectional+no_connect"))
    )
    (net (code "87") (name "unconnected-(U6-SD_DET-Pad48)") (class "Default")
      (node (ref "U6") (pin "48") (pinfunction "SD_DET_48") (pintype "bidirectional+no_connect"))
    )
    (net (code "88") (name "unconnected-(U6-SPI_CLK-Pad6)") (class "Default")
      (node (ref "U6") (pin "6") (pinfunction "SPI_CLK_6") (pintype "output+no_connect"))
    )
    (net (code "89") (name "unconnected-(U6-SPI_CS-Pad9)") (class "Default")
      (node (ref "U6") (pin "9") (pinfunction "SPI_CS_9") (pintype "output+no_connect"))
    )
    (net (code "90") (name "unconnected-(U6-SPI_MISO-Pad7)") (class "Default")
      (node (ref "U6") (pin "7") (pinfunction "SPI_MISO_7") (pintype "input+no_connect"))
    )
    (net (code "91") (name "unconnected-(U6-SPI_MOSI-Pad8)") (class "Default")
      (node (ref "U6") (pin "8") (pinfunction "SPI_MOSI_8") (pintype "output+no_connect"))
    )
    (net (code "92") (name "unconnected-(U6-USB_ID-Pad16)") (class "Default")
      (node (ref "U6") (pin "16") (pinfunction "USB_ID_16") (pintype "input+no_connect"))
    )
    (net (code "93") (name "unconnected-(U6-USIM_DET-Pad53)") (class "Default")
      (node (ref "U6") (pin "53") (pinfunction "USIM_DET_53") (pintype "bidirectional+no_connect"))
    )
    (net (code "94") (name "unconnected-(U6-VDD_AUX-Pad44)") (class "Default")
      (node (ref "U6") (pin "44") (pinfunction "VDD_AUX_44") (pintype "output+no_connect"))
    )
    (net (code "95") (name "unconnected-(U10-MOUT-Pad13)") (class "Default")
      (node (ref "U10") (pin "13") (pinfunction "MOUT_13") (pintype "output+no_connect"))
    )
    (net (code "96") (name "unconnected-(U12-SIM_VPP-PadC6)") (class "Default")
      (node (ref "U12") (pin "C6") (pinfunction "SIM_VPP_C6") (pintype "passive+no_connect"))
    )
  )
)
